# Power.net
KiCad netlist of a schematic drawn in Altium Designer
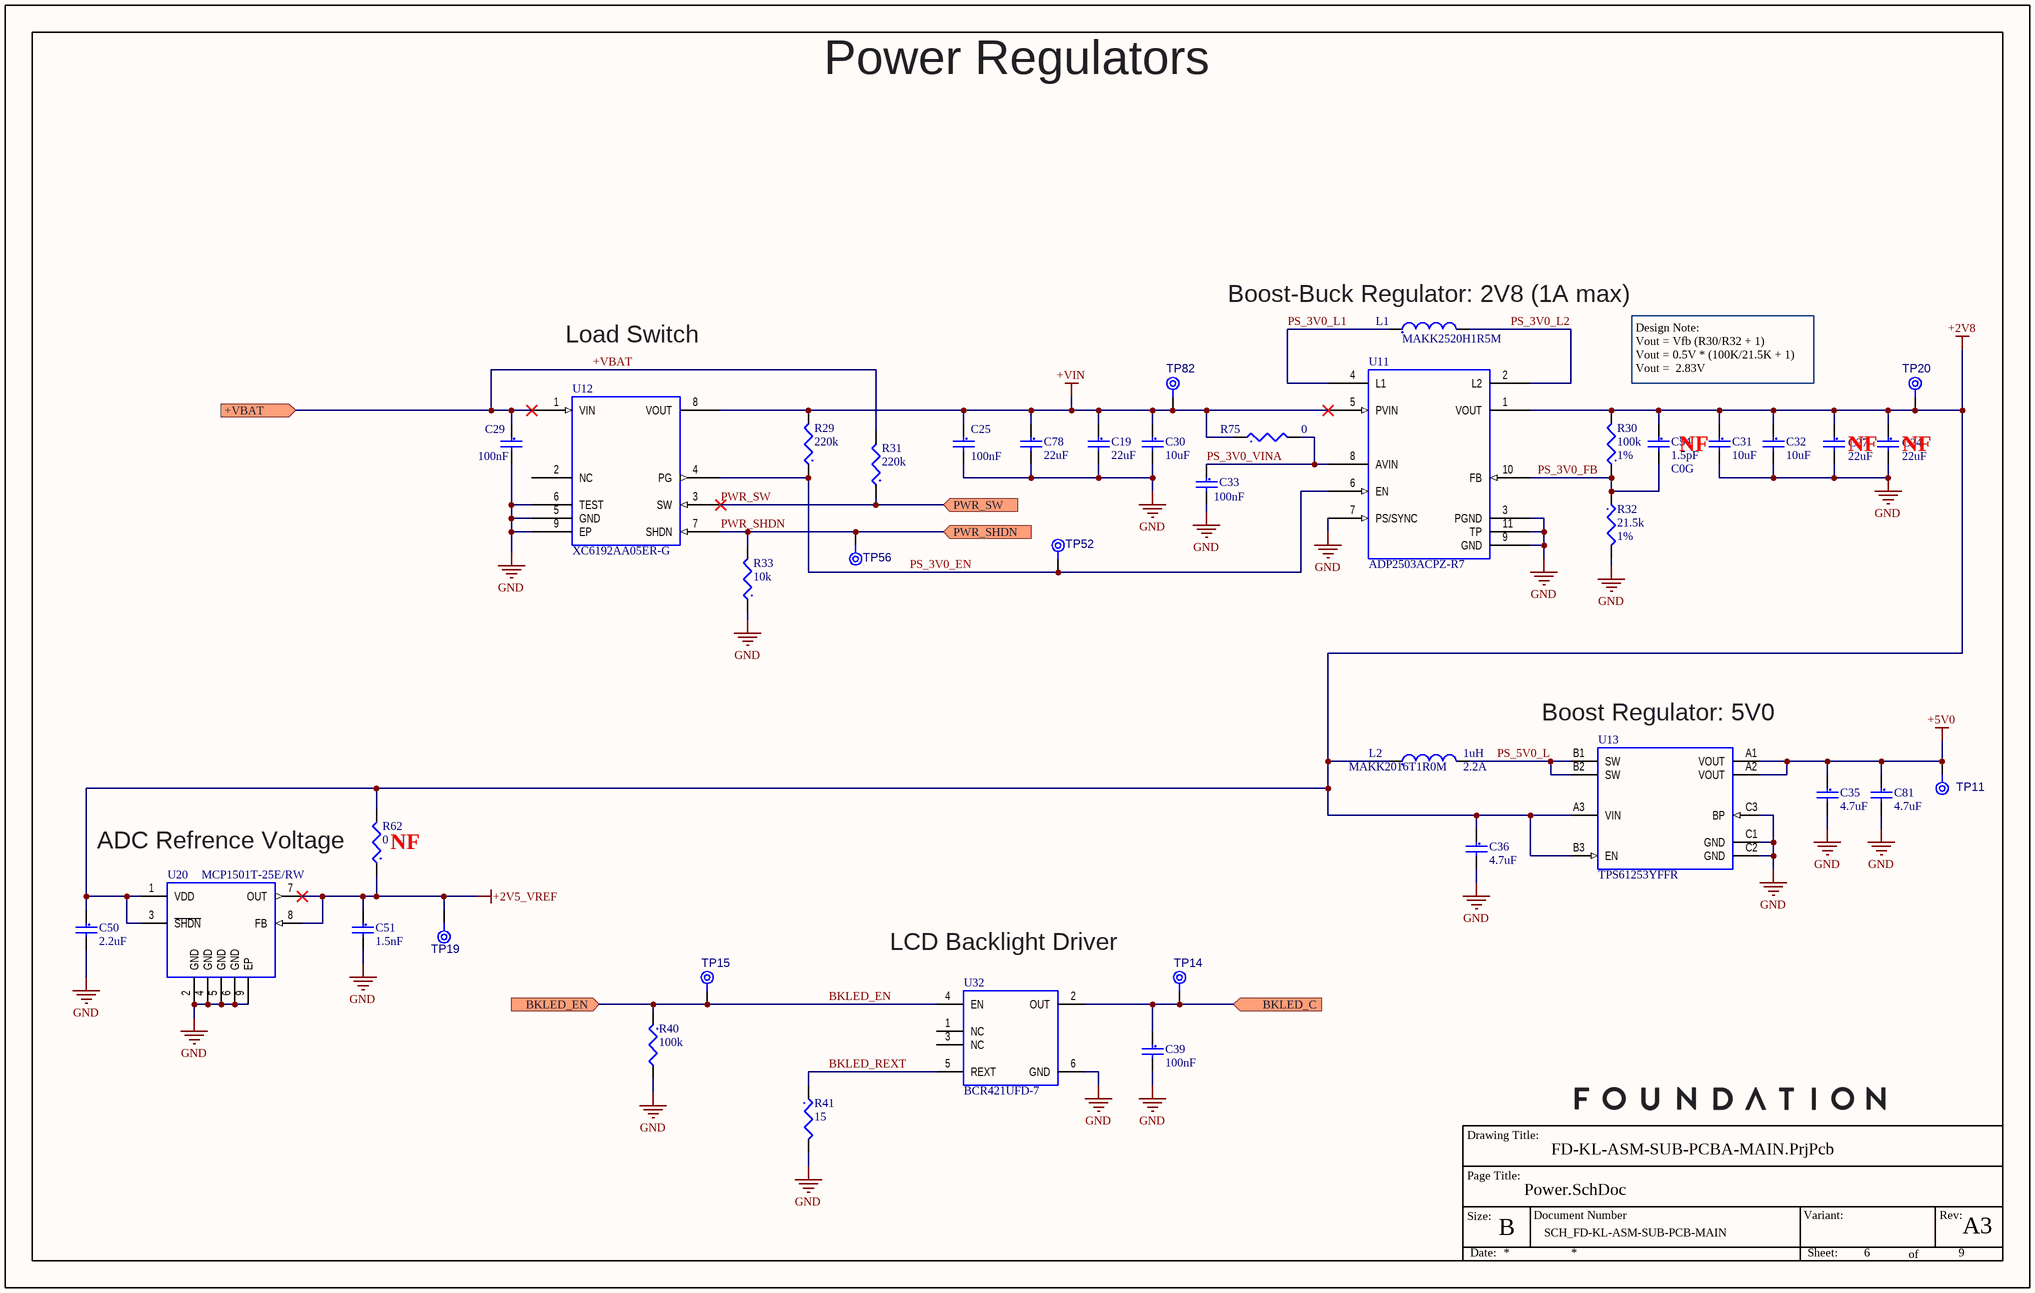
[diagram p0: Power.SchDoc]

(export (version "E")
  (design (tool "Eeschema 10.0.6"))
  (components
    (comp (ref "C19")
      (value "CAP CER 22uF 6.3V 20% X5R 0603")
      (footprint "CAPC0603(1608)90_L")
      (description "22µF ±20% 6.3V Ceramic Capacitor X5R 0603 (1608 Metric)")
      (fields
        (field (name "CAPACITANCE") "22uF")
        (field (name "VOLTAGE") "6.3V")
        (field (name "TOLERANCE") "20%")
      )
      (libsource (lib "Altium Concord Pro on A365") (part "CAP-NP-2"))
    )
    (comp (ref "C24")
      (value "CAP CER 22uF 6.3V 20% X5R 0603")
      (footprint "CAPC0603(1608)90_L")
      (description "22µF ±20% 6.3V Ceramic Capacitor X5R 0603 (1608 Metric)")
      (fields
        (field (name "CAPACITANCE") "22uF")
        (field (name "TOLERANCE") "20%")
        (field (name "VOLTAGE") "6.3V")
      )
      (libsource (lib "Altium Concord Pro on A365") (part "CAP-NP-2"))
    )
    (comp (ref "C25")
      (value "CAP CER 0.1uF 16V 10% X7R 0402")
      (footprint "CAPC0402(1005)55_L")
      (description "0.1µF ±10% 16V Ceramic Capacitor X7R 0402 (1005 Metric)")
      (fields
        (field (name "CAPACITANCE") "100nF")
        (field (name "TOLERANCE") "10%")
        (field (name "VOLTAGE") "16V")
      )
      (libsource (lib "Altium Concord Pro on A365") (part "CAP-NP-2"))
    )
    (comp (ref "C27")
      (value "CAP CER 22uF 6.3V 20% X5R 0603")
      (footprint "CAPC0603(1608)90_L")
      (description "22µF ±20% 6.3V Ceramic Capacitor X5R 0603 (1608 Metric)")
      (fields
        (field (name "CAPACITANCE") "22uF")
        (field (name "TOLERANCE") "20%")
        (field (name "VOLTAGE") "6.3V")
      )
      (libsource (lib "Altium Concord Pro on A365") (part "CAP-NP-2"))
    )
    (comp (ref "C29")
      (value "CAP CER 0.1uF 16V 10% X7R 0402")
      (footprint "CAPC0402(1005)55_L")
      (description "0.1µF ±10% 16V Ceramic Capacitor X7R 0402 (1005 Metric)")
      (fields
        (field (name "CAPACITANCE") "100nF")
        (field (name "TOLERANCE") "10%")
        (field (name "VOLTAGE") "16V")
      )
      (libsource (lib "Altium Concord Pro on A365") (part "CAP-NP-2"))
    )
    (comp (ref "C30")
      (value "CAP CER 10uF 6.3V 20% X5R 0603")
      (footprint "CAPC0603(1608)90_L")
      (description "10µF ±20% 6.3V Ceramic Capacitor X5R 0603 (1608 Metric)")
      (fields
        (field (name "CAPACITANCE") "10uF")
        (field (name "TOLERANCE") "20%")
        (field (name "VOLTAGE") "6.3V")
      )
      (libsource (lib "Altium Concord Pro on A365") (part "CAP-NP-2"))
    )
    (comp (ref "C31")
      (value "CAP CER 10uF 6.3V 20% X5R 0603")
      (footprint "CAPC0603(1608)90_L")
      (description "10µF ±20% 6.3V Ceramic Capacitor X5R 0603 (1608 Metric)")
      (fields
        (field (name "CAPACITANCE") "10uF")
        (field (name "TOLERANCE") "20%")
        (field (name "VOLTAGE") "6.3V")
      )
      (libsource (lib "Altium Concord Pro on A365") (part "CAP-NP-2"))
    )
    (comp (ref "C32")
      (value "CAP CER 10uF 6.3V 20% X5R 0603")
      (footprint "CAPC0603(1608)90_L")
      (description "10µF ±20% 6.3V Ceramic Capacitor X5R 0603 (1608 Metric)")
      (fields
        (field (name "CAPACITANCE") "10uF")
        (field (name "TOLERANCE") "20%")
        (field (name "VOLTAGE") "6.3V")
      )
      (libsource (lib "Altium Concord Pro on A365") (part "CAP-NP-2"))
    )
    (comp (ref "C33")
      (value "CAP CER 0.1uF 16V 10% X7R 0402")
      (footprint "CAPC0402(1005)55_L")
      (description "0.1µF ±10% 16V Ceramic Capacitor X7R 0402 (1005 Metric)")
      (fields
        (field (name "CAPACITANCE") "100nF")
        (field (name "TOLERANCE") "10%")
        (field (name "VOLTAGE") "16V")
      )
      (libsource (lib "Altium Concord Pro on A365") (part "CAP-NP-2"))
    )
    (comp (ref "C35")
      (value "CAP CER 4.7UF 10V 20% X5R 0402")
      (footprint "CAPC0402(1005)55_L")
      (description "4.7µF ±20% 10V Ceramic Capacitor X5R 0402 (1005 Metric)")
      (fields
        (field (name "CAPACITANCE") "4.7uF")
        (field (name "TOLERANCE") "20%")
        (field (name "VOLTAGE") "10V")
      )
      (libsource (lib "Altium Concord Pro on A365") (part "CAP-NP-2"))
    )
    (comp (ref "C36")
      (value "CAP CER 4.7UF 10V 20% X5R 0402")
      (footprint "CAPC0402(1005)55_L")
      (description "4.7µF ±20% 10V Ceramic Capacitor X5R 0402 (1005 Metric)")
      (fields
        (field (name "CAPACITANCE") "4.7uF")
        (field (name "TOLERANCE") "20%")
        (field (name "VOLTAGE") "10V")
      )
      (libsource (lib "Altium Concord Pro on A365") (part "CAP-NP-2"))
    )
    (comp (ref "C39")
      (value "CAP CER 0.1uF 16V 10% X7R 0402")
      (footprint "CAPC0402(1005)55_L")
      (description "0.1µF ±10% 16V Ceramic Capacitor X7R 0402 (1005 Metric)")
      (fields
        (field (name "CAPACITANCE") "100nF")
        (field (name "TOLERANCE") "10%")
        (field (name "VOLTAGE") "16V")
      )
      (libsource (lib "Altium Concord Pro on A365") (part "CAP-NP-2"))
    )
    (comp (ref "C50")
      (value "CAP CER 2.2uF 6.3V 10% X5R 0402")
      (footprint "CAPC0402(1005)55_L")
      (description "2.2µF ±10% 6.3V Ceramic Capacitor X5R 0402 (1005 Metric)")
      (fields (field (name "CAPACITANCE") "2.2uF") (field (name "TOLERANCE") "10%"))
      (libsource (lib "Altium Concord Pro on A365") (part "CAP-NP-2"))
    )
    (comp (ref "C51")
      (value "CAP CER 1500pF 50V 10% X7R 0402")
      (footprint "CAPC0402(1005)55_L")
      (description "1500pF ±10% 50V Ceramic Capacitor X7R 0402 (1005 Metric)")
      (fields
        (field (name "CAPACITANCE") "1.5nF")
        (field (name "VOLTAGE") "50V")
        (field (name "TOLERANCE") "10%")
      )
      (libsource (lib "Altium Concord Pro on A365") (part "CAP-NP-2"))
    )
    (comp (ref "C54")
      (value "CAP CER 1.5pF 50V C0G 0402")
      (footprint "CAPC0402(1005)55_L")
      (description "1.5pF ±0.25pF 50V Ceramic Capacitor C0G, NP0 0402 (1005 Metric)")
      (fields
        (field (name "CAPACITANCE") "1.5pF")
        (field (name "DIELECTRIC") "C0G")
        (field (name "TOLERANCE") "20%")
        (field (name "VOLTAGE") "50V")
      )
      (libsource (lib "Altium Concord Pro on A365") (part "CAP-NP-2"))
    )
    (comp (ref "C78")
      (value "CAP CER 22uF 6.3V 20% X5R 0603")
      (footprint "CAPC0603(1608)90_L")
      (description "22µF ±20% 6.3V Ceramic Capacitor X5R 0603 (1608 Metric)")
      (fields
        (field (name "CAPACITANCE") "22uF")
        (field (name "VOLTAGE") "6.3V")
        (field (name "TOLERANCE") "20%")
      )
      (libsource (lib "Altium Concord Pro on A365") (part "CAP-NP-2"))
    )
    (comp (ref "C81")
      (value "CAP CER 4.7UF 10V 20% X5R 0402")
      (footprint "CAPC0402(1005)55_L")
      (description "4.7µF ±20% 10V Ceramic Capacitor X5R 0402 (1005 Metric)")
      (fields
        (field (name "CAPACITANCE") "4.7uF")
        (field (name "TOLERANCE") "20%")
        (field (name "VOLTAGE") "10V")
      )
      (libsource (lib "Altium Concord Pro on A365") (part "CAP-NP-2"))
    )
    (comp (ref "L1")
      (value "MAKK2520H1R5M")
      (footprint "INDC1008(2520)100_V")
      (description "1.5 µH Shielded Wirewound Inductor 2.4 A 78mOhm Max 1008 (2520 Metric)")
      (libsource (lib "Altium Concord Pro on A365") (part "IND-NP-2"))
    )
    (comp (ref "L2")
      (value "MAKK2016T1R0M")
      (footprint "INDC0806(2016)100_V")
      (description "1 µH Shielded Wirewound Inductor 2.2 A 75mOhm Max 0806 (2016 Metric)")
      (fields
        (field (name "TOLERANCE") "20%")
        (field (name "INDUCTANCE-NOM (L)") "1uH")
        (field (name "RATED CURRENT-MAX") "2.2A")
      )
      (libsource (lib "Altium Concord Pro on A365") (part "IND-NP-2"))
    )
    (comp (ref "R29")
      (value "RES 220K 1/16W 1% 0402")
      (footprint "RESC0402(1005)_L")
      (description "220 kOhms ±1% 0.063W, 1/16W Chip Resistor 0402 (1005 Metric)")
      (fields (field (name "RESISTANCE") "220k") (field (name "TOLERANCE") "1%"))
      (libsource (lib "Altium Concord Pro on A365") (part "RES-2"))
    )
    (comp (ref "R30")
      (value "RES 100K 1/16W 1% 0402")
      (footprint "RESC0402(1005)_L")
      (description "100 kOhms ±1% 0.063W, 1/16W Chip Resistor 0402 (1005 Metric) Automotive AEC-Q200 Thick Film")
      (fields (field (name "RESISTANCE") "100k") (field (name "TOLERANCE") "1%"))
      (libsource (lib "Altium Concord Pro on A365") (part "RES-2"))
    )
    (comp (ref "R31")
      (value "RES 220K 1/16W 1% 0402")
      (footprint "RESC0402(1005)_L")
      (description "220 kOhms ±1% 0.063W, 1/16W Chip Resistor 0402 (1005 Metric)")
      (fields (field (name "RESISTANCE") "220k") (field (name "TOLERANCE") "1%"))
      (libsource (lib "Altium Concord Pro on A365") (part "RES-2"))
    )
    (comp (ref "R32")
      (value "RES 21.5K 1/16W 1% 0402")
      (footprint "RESC0402(1005)_L")
      (description "21.5 kOhms ±1% 0.063W, 1/16W Chip Resistor 0402 (1005 Metric)")
      (fields (field (name "RESISTANCE") "21.5k") (field (name "TOLERANCE") "1%"))
      (libsource (lib "Altium Concord Pro on A365") (part "RES-2"))
    )
    (comp (ref "R33")
      (value "RES 10K 1/16W 1% 0402")
      (footprint "RESC0402(1005)_L")
      (description "10 kOhms ±1% 0.063W, 1/16W Chip Resistor 0402 (1005 Metric)")
      (fields (field (name "RESISTANCE") "10k") (field (name "TOLERANCE") "1%"))
      (libsource (lib "Altium Concord Pro on A365") (part "RES-2"))
    )
    (comp (ref "R40")
      (value "RES 100K 1/16W 1% 0402")
      (footprint "RESC0402(1005)_L")
      (description "100 kOhms ±1% 0.063W, 1/16W Chip Resistor 0402 (1005 Metric) Automotive AEC-Q200 Thick Film")
      (fields (field (name "RESISTANCE") "100k") (field (name "TOLERANCE") "1%"))
      (libsource (lib "Altium Concord Pro on A365") (part "RES-2"))
    )
    (comp (ref "R41")
      (value "RES 15 OHM 1% 1/16W 0402")
      (footprint "RESC0402(1005)_L")
      (description "15 Ohms ±1% 0.063W, 1/16W Chip Resistor 0402 (1005 Metric)")
      (fields (field (name "RESISTANCE") "15") (field (name "POWER") "63mW") (field (name "TOLERANCE") "1%"))
      (libsource (lib "Altium Concord Pro on A365") (part "RES-2"))
    )
    (comp (ref "R62")
      (value "RES 0 OHM JUMPER 1/16W 0402")
      (footprint "RESC0402(1005)_L")
      (description "0 Ohms Jumper 0.063W, 1/16W Chip Resistor 0402 (1005 Metric)")
      (fields (field (name "RESISTANCE") "0") (field (name "TOLERANCE") "5%"))
      (libsource (lib "Altium Concord Pro on A365") (part "RES-2"))
    )
    (comp (ref "R75")
      (value "RES 0 OHM JUMPER 1/16W 0402")
      (footprint "RESC0402(1005)_L")
      (description "0 Ohms Jumper 0.063W, 1/16W Chip Resistor 0402 (1005 Metric)")
      (fields (field (name "RESISTANCE") "0") (field (name "TOLERANCE") "5%"))
      (libsource (lib "Altium Concord Pro on A365") (part "RES-2"))
    )
    (comp (ref "TP11")
      (value "TPAD8R")
      (footprint "TP08R")
      (description "0.8mm round")
      (libsource (lib "Altium Concord Pro on A365") (part "TP-R-1"))
    )
    (comp (ref "TP14")
      (value "TPAD8R")
      (footprint "TP08R")
      (description "0.8mm round")
      (libsource (lib "Altium Concord Pro on A365") (part "TP-R-1"))
    )
    (comp (ref "TP15")
      (value "TPAD8R")
      (footprint "TP08R")
      (description "0.8mm round")
      (libsource (lib "Altium Concord Pro on A365") (part "TP-R-1"))
    )
    (comp (ref "TP19")
      (value "TPAD8R")
      (footprint "TP08R")
      (description "0.8mm round")
      (libsource (lib "Altium Concord Pro on A365") (part "TP-R-1"))
    )
    (comp (ref "TP20")
      (value "TPAD8R")
      (footprint "TP08R")
      (description "0.8mm round")
      (libsource (lib "Altium Concord Pro on A365") (part "TP-R-1"))
    )
    (comp (ref "TP52")
      (value "TPAD8R")
      (footprint "TP08R")
      (description "0.8mm round")
      (libsource (lib "Altium Concord Pro on A365") (part "TP-R-1"))
    )
    (comp (ref "TP56")
      (value "TPAD8R")
      (footprint "TP08R")
      (description "0.8mm round")
      (libsource (lib "Altium Concord Pro on A365") (part "TP-R-1"))
    )
    (comp (ref "TP82")
      (value "TPAD8R")
      (footprint "TP08R")
      (description "0.8mm round")
      (libsource (lib "Altium Concord Pro on A365") (part "TP-R-1"))
    )
    (comp (ref "U11")
      (value "ADP2503ACPZ-R7")
      (footprint "ADEV - LFCSP-10_V")
      (libsource (lib "Altium Concord Pro on A365") (part "ADP2503"))
    )
    (comp (ref "U12")
      (value "XC6192AA05ER-G")
      (footprint "TORX - USP-8B06_V")
      (description "Power Switch/Driver 1:1 P-Channel 400mA USP-8B06")
      (libsource (lib "Altium Concord Pro on A365") (part "XC6192-G"))
    )
    (comp (ref "U13")
      (value "TPS61253YFFR")
      (footprint "TI - DSBGA-YFF-9_V")
      (description "Boost Switching Regulator IC Positive Fixed 5V 1 Output 3.9A (Switch) 9-UFBGA, DSBGA")
      (libsource (lib "Altium Concord Pro on A365") (part "TPS6125x"))
    )
    (comp (ref "U20")
      (value "MCP1501T-25E/RW")
      (footprint "MCHP - WDFN-8_L")
      (description "Series Voltage Reference IC 2.5V ±0.1%  8-WDFN (2x2)")
      (libsource (lib "Altium Concord Pro on A365") (part "MCP1501-xx/RW"))
    )
    (comp (ref "U32")
      (value "BCR421UFD-7")
      (footprint "DIOD - U-DFN2020-6_L")
      (description "LED Driver IC 1 Output Linear - PWM Dimming 350mA U-DFN2020-6")
      (libsource (lib "Altium Concord Pro on A365") (part "BCR421UFD-7"))
    )
  )
  (nets
    (net (code "1") (name "+2V5_VREF") (class "Default")
      (node (ref "C51") (pin "1") (pinfunction "1_1") (pintype "passive"))
      (node (ref "R62") (pin "1") (pinfunction "1_1") (pintype "passive"))
      (node (ref "TP19") (pin "1") (pinfunction "TP_1") (pintype "passive"))
      (node (ref "U20") (pin "7") (pinfunction "OUT_7") (pintype "output"))
      (node (ref "U20") (pin "8") (pinfunction "FB_8") (pintype "input"))
    )
    (net (code "2") (name "+2V8") (class "Default")
      (node (ref "C24") (pin "1") (pinfunction "1_1") (pintype "passive"))
      (node (ref "C27") (pin "1") (pinfunction "1_1") (pintype "passive"))
      (node (ref "C31") (pin "1") (pinfunction "1_1") (pintype "passive"))
      (node (ref "C32") (pin "1") (pinfunction "1_1") (pintype "passive"))
      (node (ref "C36") (pin "1") (pinfunction "1_1") (pintype "passive"))
      (node (ref "C50") (pin "1") (pinfunction "1_1") (pintype "passive"))
      (node (ref "C54") (pin "1") (pinfunction "1_1") (pintype "passive"))
      (node (ref "L2") (pin "1") (pinfunction "1_1") (pintype "passive"))
      (node (ref "R30") (pin "2") (pinfunction "2_2") (pintype "passive"))
      (node (ref "R62") (pin "2") (pinfunction "2_2") (pintype "passive"))
      (node (ref "TP20") (pin "1") (pinfunction "TP_1") (pintype "passive"))
      (node (ref "U11") (pin "1") (pinfunction "VOUT_1") (pintype "passive"))
      (node (ref "U13") (pin "A3") (pinfunction "VIN_A3") (pintype "passive"))
      (node (ref "U13") (pin "B3") (pinfunction "EN_B3") (pintype "input"))
      (node (ref "U20") (pin "1") (pinfunction "VDD_1") (pintype "power_in"))
      (node (ref "U20") (pin "3") (pinfunction "~{SHDN}_3") (pintype "passive"))
    )
    (net (code "3") (name "+5V0") (class "Default")
      (node (ref "C35") (pin "1") (pinfunction "1_1") (pintype "passive"))
      (node (ref "C81") (pin "1") (pinfunction "1_1") (pintype "passive"))
      (node (ref "TP11") (pin "1") (pinfunction "TP_1") (pintype "passive"))
      (node (ref "U13") (pin "A1") (pinfunction "VOUT_A1") (pintype "passive"))
      (node (ref "U13") (pin "A2") (pinfunction "VOUT_A2") (pintype "passive"))
    )
    (net (code "4") (name "+VIN") (class "Default")
      (node (ref "C19") (pin "1") (pinfunction "1_1") (pintype "passive"))
      (node (ref "C25") (pin "1") (pinfunction "1_1") (pintype "passive"))
      (node (ref "C30") (pin "1") (pinfunction "1_1") (pintype "passive"))
      (node (ref "C78") (pin "1") (pinfunction "1_1") (pintype "passive"))
      (node (ref "R29") (pin "2") (pinfunction "2_2") (pintype "passive"))
      (node (ref "R75") (pin "1") (pinfunction "1_1") (pintype "passive"))
      (node (ref "TP82") (pin "1") (pinfunction "TP_1") (pintype "passive"))
      (node (ref "U11") (pin "5") (pinfunction "PVIN_5") (pintype "input"))
      (node (ref "U12") (pin "8") (pinfunction "VOUT_8") (pintype "power_in"))
    )
    (net (code "5") (name "/+VBAT") (class "Default")
      (node (ref "C29") (pin "1") (pinfunction "1_1") (pintype "passive"))
      (node (ref "R31") (pin "2") (pinfunction "2_2") (pintype "passive"))
      (node (ref "U12") (pin "1") (pinfunction "VIN_1") (pintype "input"))
    )
    (net (code "6") (name "/BKLED_C") (class "Default")
      (node (ref "C39") (pin "1") (pinfunction "1_1") (pintype "passive"))
      (node (ref "TP14") (pin "1") (pinfunction "TP_1") (pintype "passive"))
      (node (ref "U32") (pin "2") (pinfunction "OUT_2") (pintype "passive"))
    )
    (net (code "7") (name "/BKLED_EN") (class "Default")
      (node (ref "R40") (pin "1") (pinfunction "1_1") (pintype "passive"))
      (node (ref "TP15") (pin "1") (pinfunction "TP_1") (pintype "passive"))
      (node (ref "U32") (pin "4") (pinfunction "EN_4") (pintype "passive"))
    )
    (net (code "8") (name "/BKLED_REXT") (class "Default")
      (node (ref "R41") (pin "1") (pinfunction "1_1") (pintype "passive"))
      (node (ref "U32") (pin "5") (pinfunction "REXT_5") (pintype "passive"))
    )
    (net (code "9") (name "/PS_3V0_EN") (class "Default")
      (node (ref "R29") (pin "1") (pinfunction "1_1") (pintype "passive"))
      (node (ref "TP52") (pin "1") (pinfunction "TP_1") (pintype "passive"))
      (node (ref "U11") (pin "6") (pinfunction "EN_6") (pintype "input"))
      (node (ref "U12") (pin "4") (pinfunction "PG_4") (pintype "output"))
    )
    (net (code "10") (name "/PS_3V0_FB") (class "Default")
      (node (ref "C54") (pin "2") (pinfunction "2_2") (pintype "passive"))
      (node (ref "R30") (pin "1") (pinfunction "1_1") (pintype "passive"))
      (node (ref "R32") (pin "1") (pinfunction "1_1") (pintype "passive"))
      (node (ref "U11") (pin "10") (pinfunction "FB_10") (pintype "input"))
    )
    (net (code "11") (name "/PS_3V0_L1") (class "Default")
      (node (ref "L1") (pin "1") (pinfunction "1_1") (pintype "passive"))
      (node (ref "U11") (pin "4") (pinfunction "L1_4") (pintype "passive"))
    )
    (net (code "12") (name "/PS_3V0_L2") (class "Default")
      (node (ref "L1") (pin "2") (pinfunction "2_2") (pintype "passive"))
      (node (ref "U11") (pin "2") (pinfunction "L2_2") (pintype "passive"))
    )
    (net (code "13") (name "/PS_3V0_VINA") (class "Default")
      (node (ref "C33") (pin "1") (pinfunction "1_1") (pintype "passive"))
      (node (ref "R75") (pin "2") (pinfunction "2_2") (pintype "passive"))
      (node (ref "U11") (pin "8") (pinfunction "AVIN_8") (pintype "power_in"))
    )
    (net (code "14") (name "/PS_5V0_L") (class "Default")
      (node (ref "L2") (pin "2") (pinfunction "2_2") (pintype "passive"))
      (node (ref "U13") (pin "B1") (pinfunction "SW_B1") (pintype "passive"))
      (node (ref "U13") (pin "B2") (pinfunction "SW_B2") (pintype "passive"))
    )
    (net (code "15") (name "/PWR_SHDN") (class "Default")
      (node (ref "R33") (pin "2") (pinfunction "2_2") (pintype "passive"))
      (node (ref "TP56") (pin "1") (pinfunction "TP_1") (pintype "passive"))
      (node (ref "U12") (pin "7") (pinfunction "SHDN_7") (pintype "input"))
    )
    (net (code "16") (name "/PWR_SW") (class "Default")
      (node (ref "R31") (pin "1") (pinfunction "1_1") (pintype "passive"))
      (node (ref "U12") (pin "3") (pinfunction "SW_3") (pintype "input"))
    )
    (net (code "17") (name "GND") (class "Default")
      (node (ref "C19") (pin "2") (pinfunction "2_2") (pintype "passive"))
      (node (ref "C24") (pin "2") (pinfunction "2_2") (pintype "passive"))
      (node (ref "C25") (pin "2") (pinfunction "2_2") (pintype "passive"))
      (node (ref "C27") (pin "2") (pinfunction "2_2") (pintype "passive"))
      (node (ref "C29") (pin "2") (pinfunction "2_2") (pintype "passive"))
      (node (ref "C30") (pin "2") (pinfunction "2_2") (pintype "passive"))
      (node (ref "C31") (pin "2") (pinfunction "2_2") (pintype "passive"))
      (node (ref "C32") (pin "2") (pinfunction "2_2") (pintype "passive"))
      (node (ref "C33") (pin "2") (pinfunction "2_2") (pintype "passive"))
      (node (ref "C35") (pin "2") (pinfunction "2_2") (pintype "passive"))
      (node (ref "C36") (pin "2") (pinfunction "2_2") (pintype "passive"))
      (node (ref "C39") (pin "2") (pinfunction "2_2") (pintype "passive"))
      (node (ref "C50") (pin "2") (pinfunction "2_2") (pintype "passive"))
      (node (ref "C51") (pin "2") (pinfunction "2_2") (pintype "passive"))
      (node (ref "C78") (pin "2") (pinfunction "2_2") (pintype "passive"))
      (node (ref "C81") (pin "2") (pinfunction "2_2") (pintype "passive"))
      (node (ref "R32") (pin "2") (pinfunction "2_2") (pintype "passive"))
      (node (ref "R33") (pin "1") (pinfunction "1_1") (pintype "passive"))
      (node (ref "R40") (pin "2") (pinfunction "2_2") (pintype "passive"))
      (node (ref "R41") (pin "2") (pinfunction "2_2") (pintype "passive"))
      (node (ref "U11") (pin "11") (pinfunction "TP_11") (pintype "passive"))
      (node (ref "U11") (pin "3") (pinfunction "PGND_3") (pintype "power_in"))
      (node (ref "U11") (pin "7") (pinfunction "PS/SYNC_7") (pintype "input"))
      (node (ref "U11") (pin "9") (pinfunction "GND_9") (pintype "power_in"))
      (node (ref "U12") (pin "5") (pinfunction "GND_5") (pintype "power_in"))
      (node (ref "U12") (pin "6") (pinfunction "TEST_6") (pintype "passive"))
      (node (ref "U12") (pin "9") (pinfunction "EP_9") (pintype "power_in"))
      (node (ref "U13") (pin "C1") (pinfunction "GND_C1") (pintype "passive"))
      (node (ref "U13") (pin "C2") (pinfunction "GND_C2") (pintype "passive"))
      (node (ref "U13") (pin "C3") (pinfunction "BP_C3") (pintype "input"))
      (node (ref "U20") (pin "2") (pinfunction "GND_2") (pintype "power_in"))
      (node (ref "U20") (pin "4") (pinfunction "GND_4") (pintype "power_in"))
      (node (ref "U20") (pin "5") (pinfunction "GND_5") (pintype "power_in"))
      (node (ref "U20") (pin "6") (pinfunction "GND_6") (pintype "power_in"))
      (node (ref "U20") (pin "9") (pinfunction "EP_9") (pintype "power_in"))
      (node (ref "U32") (pin "6") (pinfunction "GND_6") (pintype "passive"))
    )
    (net (code "18") (name "unconnected-(U12-NC-Pad2)") (class "Default")
      (node (ref "U12") (pin "2") (pinfunction "NC_2") (pintype "passive"))
    )
    (net (code "19") (name "unconnected-(U32-NC-Pad1)") (class "Default")
      (node (ref "U32") (pin "1") (pinfunction "NC_1") (pintype "passive"))
    )
    (net (code "20") (name "unconnected-(U32-NC-Pad3)") (class "Default")
      (node (ref "U32") (pin "3") (pinfunction "NC_3") (pintype "passive"))
    )
  )
)
